# led_column.net
KiCad netlist of a schematic drawn in Altium Designer
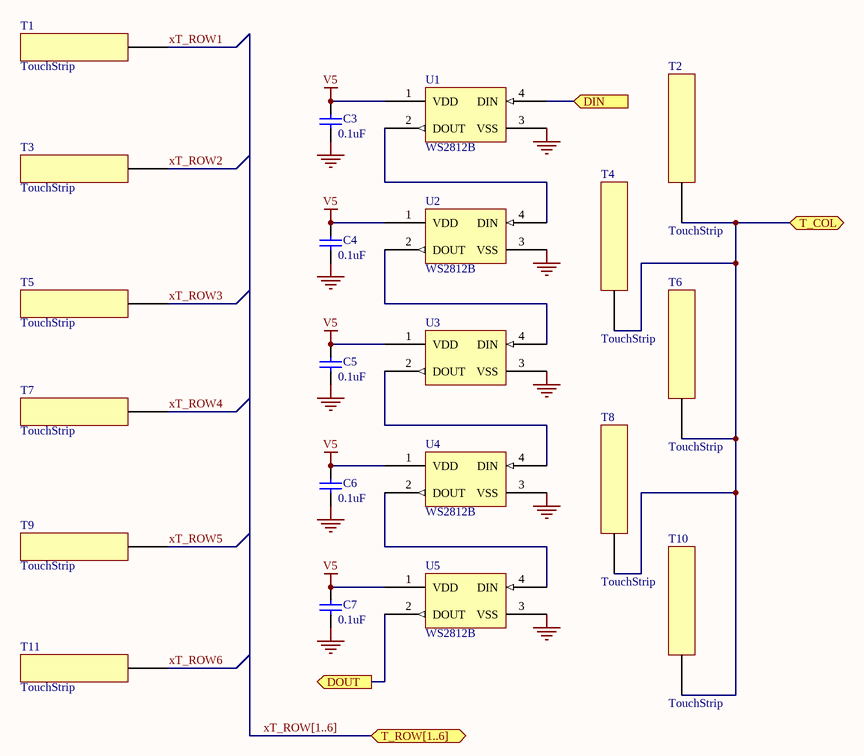
[diagram p0: led_column.SchDoc]

(export (version "E")
  (design (tool "Eeschema 10.0.6"))
  (components
    (comp (ref "C3")
      (value "0.1uF")
      (footprint "CAPC2012L")
      (description "Capacitor")
      (fields (field (name "PUBLISHER") "Altium Limited"))
      (libsource (lib "*") (part "Cap"))
    )
    (comp (ref "C4")
      (value "0.1uF")
      (footprint "CAPC2012L")
      (description "Capacitor")
      (fields (field (name "PUBLISHER") "Altium Limited"))
      (libsource (lib "*") (part "Cap"))
    )
    (comp (ref "C5")
      (value "0.1uF")
      (footprint "CAPC2012L")
      (description "Capacitor")
      (fields (field (name "PUBLISHER") "Altium Limited"))
      (libsource (lib "*") (part "Cap"))
    )
    (comp (ref "C6")
      (value "0.1uF")
      (footprint "CAPC2012L")
      (description "Capacitor")
      (fields (field (name "PUBLISHER") "Altium Limited"))
      (libsource (lib "*") (part "Cap"))
    )
    (comp (ref "C7")
      (value "0.1uF")
      (footprint "CAPC2012L")
      (description "Capacitor")
      (fields (field (name "PUBLISHER") "Altium Limited"))
      (libsource (lib "*") (part "Cap"))
    )
    (comp (ref "T1")
      (value "TouchStrip")
      (footprint "TouchStrip")
      (libsource (lib "components_top") (part "TouchStrip"))
    )
    (comp (ref "T2") (value "TouchStrip") (footprint "TouchStrip") (libsource (lib "") (part "TouchStrip_1")))
    (comp (ref "T3")
      (value "TouchStrip")
      (footprint "TouchStrip")
      (libsource (lib "components_top") (part "TouchStrip"))
    )
    (comp (ref "T4") (value "TouchStrip") (footprint "TouchStrip") (libsource (lib "") (part "TouchStrip_1")))
    (comp (ref "T5")
      (value "TouchStrip")
      (footprint "TouchStrip")
      (libsource (lib "components_top") (part "TouchStrip"))
    )
    (comp (ref "T6") (value "TouchStrip") (footprint "TouchStrip") (libsource (lib "") (part "TouchStrip_1")))
    (comp (ref "T7")
      (value "TouchStrip")
      (footprint "TouchStrip")
      (libsource (lib "components_top") (part "TouchStrip"))
    )
    (comp (ref "T8") (value "TouchStrip") (footprint "TouchStrip") (libsource (lib "") (part "TouchStrip_1")))
    (comp (ref "T9")
      (value "TouchStrip")
      (footprint "TouchStrip")
      (libsource (lib "components_top") (part "TouchStrip"))
    )
    (comp (ref "T10")
      (value "TouchStrip")
      (footprint "TouchStrip")
      (libsource (lib "") (part "TouchStrip_1"))
    )
    (comp (ref "T11")
      (value "TouchStrip")
      (footprint "TouchStrip")
      (libsource (lib "components_top") (part "TouchStrip"))
    )
    (comp (ref "U1")
      (value "WS2812B")
      (footprint "WS2812B")
      (libsource (lib "components_top") (part "WS2812B"))
    )
    (comp (ref "U2")
      (value "WS2812B")
      (footprint "WS2812B")
      (libsource (lib "components_top") (part "WS2812B"))
    )
    (comp (ref "U3") (value "~") (footprint "WS2812B") (libsource (lib "components_top") (part "WS2812B")))
    (comp (ref "U4")
      (value "WS2812B")
      (footprint "WS2812B")
      (libsource (lib "components_top") (part "WS2812B"))
    )
    (comp (ref "U5")
      (value "WS2812B")
      (footprint "WS2812B")
      (libsource (lib "components_top") (part "WS2812B"))
    )
  )
  (nets
    (net (code "1") (name "/DIN") (class "Default")
      (node (ref "U1") (pin "4") (pinfunction "DIN_4") (pintype "input"))
    )
    (net (code "2") (name "/DOUT") (class "Default")
      (node (ref "U5") (pin "2") (pinfunction "DOUT_2") (pintype "output"))
    )
    (net (code "3") (name "/T_COL") (class "Default")
      (node (ref "T10") (pin "0") (pinfunction "0_0") (pintype "passive"))
      (node (ref "T2") (pin "0") (pinfunction "0_0") (pintype "passive"))
      (node (ref "T4") (pin "0") (pinfunction "0_0") (pintype "passive"))
      (node (ref "T6") (pin "0") (pinfunction "0_0") (pintype "passive"))
      (node (ref "T8") (pin "0") (pinfunction "0_0") (pintype "passive"))
    )
    (net (code "4") (name "/xT_ROW1") (class "Default")
      (node (ref "T1") (pin "0") (pinfunction "0_0") (pintype "passive"))
    )
    (net (code "5") (name "/xT_ROW2") (class "Default")
      (node (ref "T3") (pin "0") (pinfunction "0_0") (pintype "passive"))
    )
    (net (code "6") (name "/xT_ROW3") (class "Default")
      (node (ref "T5") (pin "0") (pinfunction "0_0") (pintype "passive"))
    )
    (net (code "7") (name "/xT_ROW4") (class "Default")
      (node (ref "T7") (pin "0") (pinfunction "0_0") (pintype "passive"))
    )
    (net (code "8") (name "/xT_ROW5") (class "Default")
      (node (ref "T9") (pin "0") (pinfunction "0_0") (pintype "passive"))
    )
    (net (code "9") (name "/xT_ROW6") (class "Default")
      (node (ref "T11") (pin "0") (pinfunction "0_0") (pintype "passive"))
    )
    (net (code "11") (name "GND") (class "Default")
      (node (ref "C3") (pin "2") (pinfunction "2_2") (pintype "passive"))
      (node (ref "C4") (pin "2") (pinfunction "2_2") (pintype "passive"))
      (node (ref "C5") (pin "2") (pinfunction "2_2") (pintype "passive"))
      (node (ref "C6") (pin "2") (pinfunction "2_2") (pintype "passive"))
      (node (ref "C7") (pin "2") (pinfunction "2_2") (pintype "passive"))
      (node (ref "U1") (pin "3") (pinfunction "VSS_3") (pintype "power_in"))
      (node (ref "U2") (pin "3") (pinfunction "VSS_3") (pintype "power_in"))
      (node (ref "U3") (pin "3") (pinfunction "VSS_3") (pintype "power_in"))
      (node (ref "U4") (pin "3") (pinfunction "VSS_3") (pintype "power_in"))
      (node (ref "U5") (pin "3") (pinfunction "VSS_3") (pintype "power_in"))
    )
    (net (code "12") (name "Net-(U1-DOUT)") (class "Default")
      (node (ref "U1") (pin "2") (pinfunction "DOUT_2") (pintype "output"))
      (node (ref "U2") (pin "4") (pinfunction "DIN_4") (pintype "input"))
    )
    (net (code "13") (name "Net-(U2-DOUT)") (class "Default")
      (node (ref "U2") (pin "2") (pinfunction "DOUT_2") (pintype "output"))
      (node (ref "U3") (pin "4") (pinfunction "DIN_4") (pintype "input"))
    )
    (net (code "14") (name "Net-(U3-DOUT)") (class "Default")
      (node (ref "U3") (pin "2") (pinfunction "DOUT_2") (pintype "output"))
      (node (ref "U4") (pin "4") (pinfunction "DIN_4") (pintype "input"))
    )
    (net (code "15") (name "Net-(U4-DOUT)") (class "Default")
      (node (ref "U4") (pin "2") (pinfunction "DOUT_2") (pintype "output"))
      (node (ref "U5") (pin "4") (pinfunction "DIN_4") (pintype "input"))
    )
    (net (code "16") (name "V5") (class "Default")
      (node (ref "C3") (pin "1") (pinfunction "1_1") (pintype "passive"))
      (node (ref "C4") (pin "1") (pinfunction "1_1") (pintype "passive"))
      (node (ref "C5") (pin "1") (pinfunction "1_1") (pintype "passive"))
      (node (ref "C6") (pin "1") (pinfunction "1_1") (pintype "passive"))
      (node (ref "C7") (pin "1") (pinfunction "1_1") (pintype "passive"))
      (node (ref "U1") (pin "1") (pinfunction "VDD_1") (pintype "power_in"))
      (node (ref "U2") (pin "1") (pinfunction "VDD_1") (pintype "power_in"))
      (node (ref "U3") (pin "1") (pinfunction "VDD_1") (pintype "power_in"))
      (node (ref "U4") (pin "1") (pinfunction "VDD_1") (pintype "power_in"))
      (node (ref "U5") (pin "1") (pinfunction "VDD_1") (pintype "power_in"))
    )
  )
)
